# PCB-Logic-1_1-in-wall-IoT-Switch-Logic-B.net
KiCad netlist of a schematic drawn in EAGLE
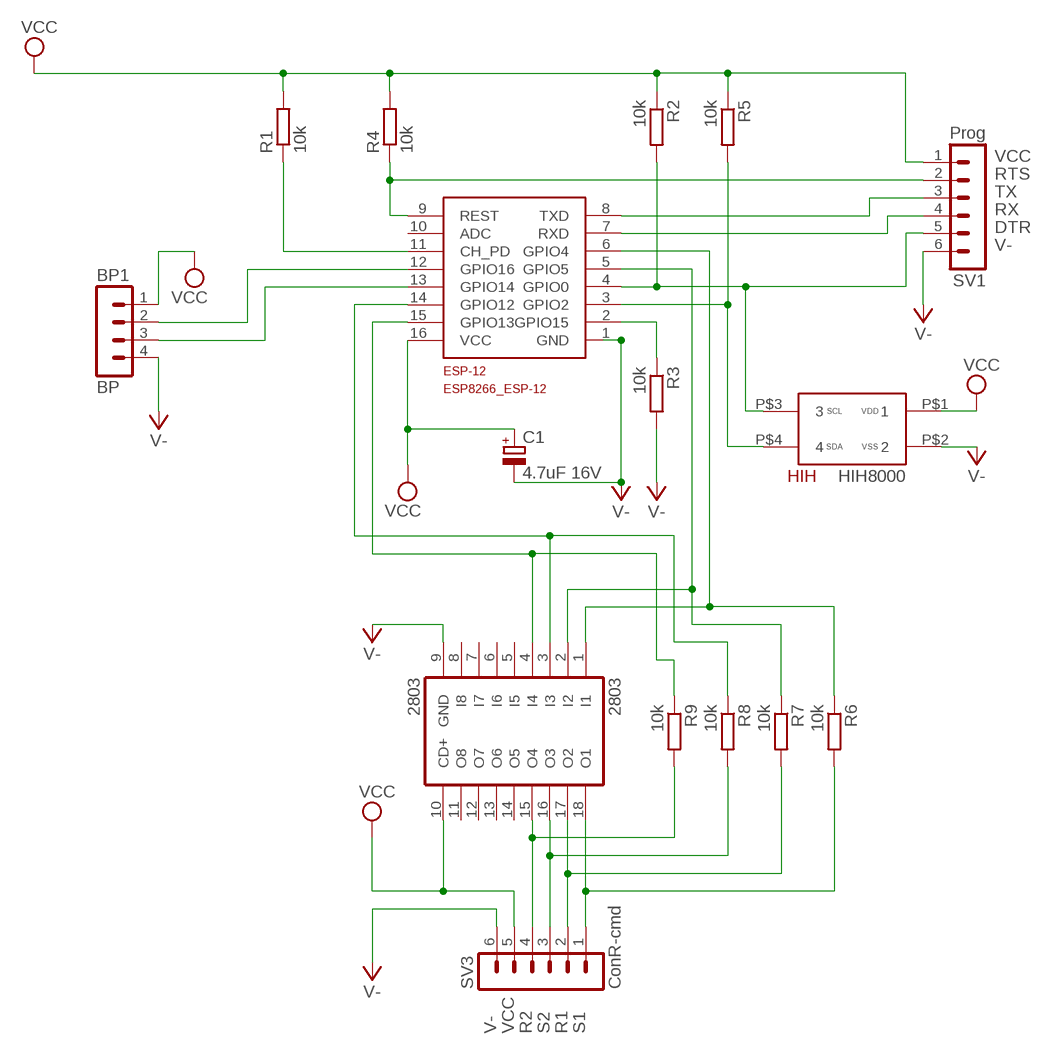
[diagram p0: schematic, sheet 1]

(export (version "E")
  (design (tool "Eeschema 10.0.6"))
  (components
    (comp (ref "2803")
      (value "2803")
      (footprint "eagle-import:SO18W")
      (libsource (lib "eagle-import") (part "ULN2803ADWADW"))
    )
    (comp (ref "BP")
      (value "BP1")
      (footprint "eagle-import:MA04-1")
      (libsource (lib "eagle-import") (part "MA04-1"))
    )
    (comp (ref "C1")
      (value "4.7uF 16V")
      (footprint "eagle-import:A_3216-18W")
      (libsource (lib "eagle-import") (part "CPOL-EUA/3216-18W"))
    )
    (comp (ref "ESP-12")
      (value "ESP8266_ESP-12")
      (footprint "eagle-import:ESP8266-ESP12")
      (libsource (lib "eagle-import") (part "ESP8266_ESP-12"))
    )
    (comp (ref "HIH")
      (value "HIH8120-021-001")
      (footprint "eagle-import:SIP4")
      (libsource (lib "eagle-import") (part "HIH8121-021-001"))
    )
    (comp (ref "R1")
      (value "10k")
      (footprint "eagle-import:R1206W")
      (libsource (lib "eagle-import") (part "R-EU_R1206W"))
    )
    (comp (ref "R2")
      (value "10k")
      (footprint "eagle-import:R1206W")
      (libsource (lib "eagle-import") (part "R-EU_R1206W"))
    )
    (comp (ref "R3")
      (value "10k")
      (footprint "eagle-import:R1206W")
      (libsource (lib "eagle-import") (part "R-EU_R1206W"))
    )
    (comp (ref "R4")
      (value "10k")
      (footprint "eagle-import:R1206W")
      (libsource (lib "eagle-import") (part "R-EU_R1206W"))
    )
    (comp (ref "R5")
      (value "10k")
      (footprint "eagle-import:R1206W")
      (libsource (lib "eagle-import") (part "R-EU_R1206W"))
    )
    (comp (ref "R6")
      (value "10k")
      (footprint "eagle-import:R1206W")
      (libsource (lib "eagle-import") (part "R-EU_R1206W"))
    )
    (comp (ref "R7")
      (value "10k")
      (footprint "eagle-import:R1206W")
      (libsource (lib "eagle-import") (part "R-EU_R1206W"))
    )
    (comp (ref "R8")
      (value "10k")
      (footprint "eagle-import:R1206W")
      (libsource (lib "eagle-import") (part "R-EU_R1206W"))
    )
    (comp (ref "R9")
      (value "10k")
      (footprint "eagle-import:R1206W")
      (libsource (lib "eagle-import") (part "R-EU_R1206W"))
    )
    (comp (ref "SV1")
      (value "Prog")
      (footprint "eagle-import:MA06-1")
      (libsource (lib "eagle-import") (part "MA06-1"))
    )
    (comp (ref "SV3")
      (value "ConR-cmd")
      (footprint "eagle-import:MA06-1")
      (libsource (lib "eagle-import") (part "MA06-1"))
    )
  )
  (nets
    (net (code "1") (name "/DTR") (class "Default")
      (node (ref "ESP-12") (pin "4") (pinfunction "GPIO0_4") (pintype "bidirectional"))
      (node (ref "HIH") (pin "P$3") (pinfunction "3_P$3") (pintype "bidirectional"))
      (node (ref "R2") (pin "2") (pinfunction "2_2") (pintype "passive"))
      (node (ref "SV1") (pin "5") (pinfunction "5_5") (pintype "passive"))
    )
    (net (code "2") (name "/R1") (class "Default")
      (node (ref "2803") (pin "17") (pinfunction "O2_17") (pintype "open_collector"))
      (node (ref "R7") (pin "2") (pinfunction "2_2") (pintype "passive"))
      (node (ref "SV3") (pin "2") (pinfunction "2_2") (pintype "passive"))
    )
    (net (code "3") (name "/R2") (class "Default")
      (node (ref "2803") (pin "15") (pinfunction "O4_15") (pintype "open_collector"))
      (node (ref "R9") (pin "2") (pinfunction "2_2") (pintype "passive"))
      (node (ref "SV3") (pin "4") (pinfunction "4_4") (pintype "passive"))
    )
    (net (code "4") (name "/RTS") (class "Default")
      (node (ref "ESP-12") (pin "9") (pinfunction "REST_9") (pintype "bidirectional"))
      (node (ref "R4") (pin "1") (pinfunction "1_1") (pintype "passive"))
      (node (ref "SV1") (pin "2") (pinfunction "2_2") (pintype "passive"))
    )
    (net (code "5") (name "/RX") (class "Default")
      (node (ref "ESP-12") (pin "7") (pinfunction "RXD_7") (pintype "bidirectional"))
      (node (ref "SV1") (pin "4") (pinfunction "4_4") (pintype "passive"))
    )
    (net (code "6") (name "/S1") (class "Default")
      (node (ref "2803") (pin "18") (pinfunction "O1_18") (pintype "open_collector"))
      (node (ref "R6") (pin "2") (pinfunction "2_2") (pintype "passive"))
      (node (ref "SV3") (pin "1") (pinfunction "1_1") (pintype "passive"))
    )
    (net (code "7") (name "/S2") (class "Default")
      (node (ref "2803") (pin "16") (pinfunction "O3_16") (pintype "open_collector"))
      (node (ref "R8") (pin "2") (pinfunction "2_2") (pintype "passive"))
      (node (ref "SV3") (pin "3") (pinfunction "3_3") (pintype "passive"))
    )
    (net (code "8") (name "/TX") (class "Default")
      (node (ref "ESP-12") (pin "8") (pinfunction "TXD_8") (pintype "bidirectional"))
      (node (ref "SV1") (pin "3") (pinfunction "3_3") (pintype "passive"))
    )
    (net (code "9") (name "Net-(2803-I1)") (class "Default")
      (node (ref "2803") (pin "1") (pinfunction "I1_1") (pintype "input"))
      (node (ref "ESP-12") (pin "6") (pinfunction "GPIO4_6") (pintype "bidirectional"))
      (node (ref "R6") (pin "1") (pinfunction "1_1") (pintype "passive"))
    )
    (net (code "10") (name "Net-(2803-I2)") (class "Default")
      (node (ref "2803") (pin "2") (pinfunction "I2_2") (pintype "input"))
      (node (ref "ESP-12") (pin "5") (pinfunction "GPIO5_5") (pintype "bidirectional"))
      (node (ref "R7") (pin "1") (pinfunction "1_1") (pintype "passive"))
    )
    (net (code "11") (name "Net-(2803-I3)") (class "Default")
      (node (ref "2803") (pin "3") (pinfunction "I3_3") (pintype "input"))
      (node (ref "ESP-12") (pin "14") (pinfunction "GPIO12_14") (pintype "bidirectional"))
      (node (ref "R8") (pin "1") (pinfunction "1_1") (pintype "passive"))
    )
    (net (code "12") (name "Net-(2803-I4)") (class "Default")
      (node (ref "2803") (pin "4") (pinfunction "I4_4") (pintype "input"))
      (node (ref "ESP-12") (pin "15") (pinfunction "GPIO13_15") (pintype "bidirectional"))
      (node (ref "R9") (pin "1") (pinfunction "1_1") (pintype "passive"))
    )
    (net (code "13") (name "Net-(ESP-12-CH_PD)") (class "Default")
      (node (ref "ESP-12") (pin "11") (pinfunction "CH_PD_11") (pintype "bidirectional"))
      (node (ref "R1") (pin "1") (pinfunction "1_1") (pintype "passive"))
    )
    (net (code "14") (name "Net-(ESP-12-GPIO2)") (class "Default")
      (node (ref "ESP-12") (pin "3") (pinfunction "GPIO2_3") (pintype "bidirectional"))
      (node (ref "HIH") (pin "P$4") (pinfunction "4_P$4") (pintype "bidirectional"))
      (node (ref "R5") (pin "2") (pinfunction "2_2") (pintype "passive"))
    )
    (net (code "15") (name "Net-(ESP-12-GPIO14)") (class "Default")
      (node (ref "BP") (pin "3") (pinfunction "3_3") (pintype "passive"))
      (node (ref "ESP-12") (pin "13") (pinfunction "GPIO14_13") (pintype "bidirectional"))
    )
    (net (code "16") (name "Net-(ESP-12-GPIO15)") (class "Default")
      (node (ref "ESP-12") (pin "2") (pinfunction "GPIO15_2") (pintype "bidirectional"))
      (node (ref "R3") (pin "1") (pinfunction "1_1") (pintype "passive"))
    )
    (net (code "17") (name "Net-(ESP-12-GPIO16)") (class "Default")
      (node (ref "BP") (pin "2") (pinfunction "2_2") (pintype "passive"))
      (node (ref "ESP-12") (pin "12") (pinfunction "GPIO16_12") (pintype "bidirectional"))
    )
    (net (code "18") (name "V-") (class "Default")
      (node (ref "2803") (pin "9") (pinfunction "GND_9") (pintype "power_in"))
      (node (ref "BP") (pin "4") (pinfunction "4_4") (pintype "passive"))
      (node (ref "C1") (pin "-") (pinfunction "-_-") (pintype "passive"))
      (node (ref "ESP-12") (pin "1") (pinfunction "GND_1") (pintype "bidirectional"))
      (node (ref "HIH") (pin "P$2") (pinfunction "2_P$2") (pintype "bidirectional"))
      (node (ref "R3") (pin "2") (pinfunction "2_2") (pintype "passive"))
      (node (ref "SV1") (pin "6") (pinfunction "6_6") (pintype "passive"))
      (node (ref "SV3") (pin "6") (pinfunction "6_6") (pintype "passive"))
    )
    (net (code "19") (name "VCC") (class "Default")
      (node (ref "2803") (pin "10") (pinfunction "CD+_10") (pintype "passive"))
      (node (ref "BP") (pin "1") (pinfunction "1_1") (pintype "passive"))
      (node (ref "C1") (pin "+") (pinfunction "+_+") (pintype "passive"))
      (node (ref "ESP-12") (pin "16") (pinfunction "VCC_16") (pintype "bidirectional"))
      (node (ref "HIH") (pin "P$1") (pinfunction "1_P$1") (pintype "bidirectional"))
      (node (ref "R1") (pin "2") (pinfunction "2_2") (pintype "passive"))
      (node (ref "R2") (pin "1") (pinfunction "1_1") (pintype "passive"))
      (node (ref "R4") (pin "2") (pinfunction "2_2") (pintype "passive"))
      (node (ref "R5") (pin "1") (pinfunction "1_1") (pintype "passive"))
      (node (ref "SV1") (pin "1") (pinfunction "1_1") (pintype "passive"))
      (node (ref "SV3") (pin "5") (pinfunction "5_5") (pintype "passive"))
    )
    (net (code "20") (name "unconnected-(2803-I5-Pad5)") (class "Default")
      (node (ref "2803") (pin "5") (pinfunction "I5_5") (pintype "input"))
    )
    (net (code "21") (name "unconnected-(2803-I6-Pad6)") (class "Default")
      (node (ref "2803") (pin "6") (pinfunction "I6_6") (pintype "input"))
    )
    (net (code "22") (name "unconnected-(2803-I7-Pad7)") (class "Default")
      (node (ref "2803") (pin "7") (pinfunction "I7_7") (pintype "input"))
    )
    (net (code "23") (name "unconnected-(2803-I8-Pad8)") (class "Default")
      (node (ref "2803") (pin "8") (pinfunction "I8_8") (pintype "input"))
    )
    (net (code "24") (name "unconnected-(2803-O5-Pad14)") (class "Default")
      (node (ref "2803") (pin "14") (pinfunction "O5_14") (pintype "open_collector"))
    )
    (net (code "25") (name "unconnected-(2803-O6-Pad13)") (class "Default")
      (node (ref "2803") (pin "13") (pinfunction "O6_13") (pintype "open_collector"))
    )
    (net (code "26") (name "unconnected-(2803-O7-Pad12)") (class "Default")
      (node (ref "2803") (pin "12") (pinfunction "O7_12") (pintype "open_collector"))
    )
    (net (code "27") (name "unconnected-(2803-O8-Pad11)") (class "Default")
      (node (ref "2803") (pin "11") (pinfunction "O8_11") (pintype "open_collector"))
    )
    (net (code "28") (name "unconnected-(ESP-12-ADC-Pad10)") (class "Default")
      (node (ref "ESP-12") (pin "10") (pinfunction "ADC_10") (pintype "bidirectional"))
    )
  )
)
